# DASHBOARD.net
KiCad netlist of a schematic drawn in EAGLE
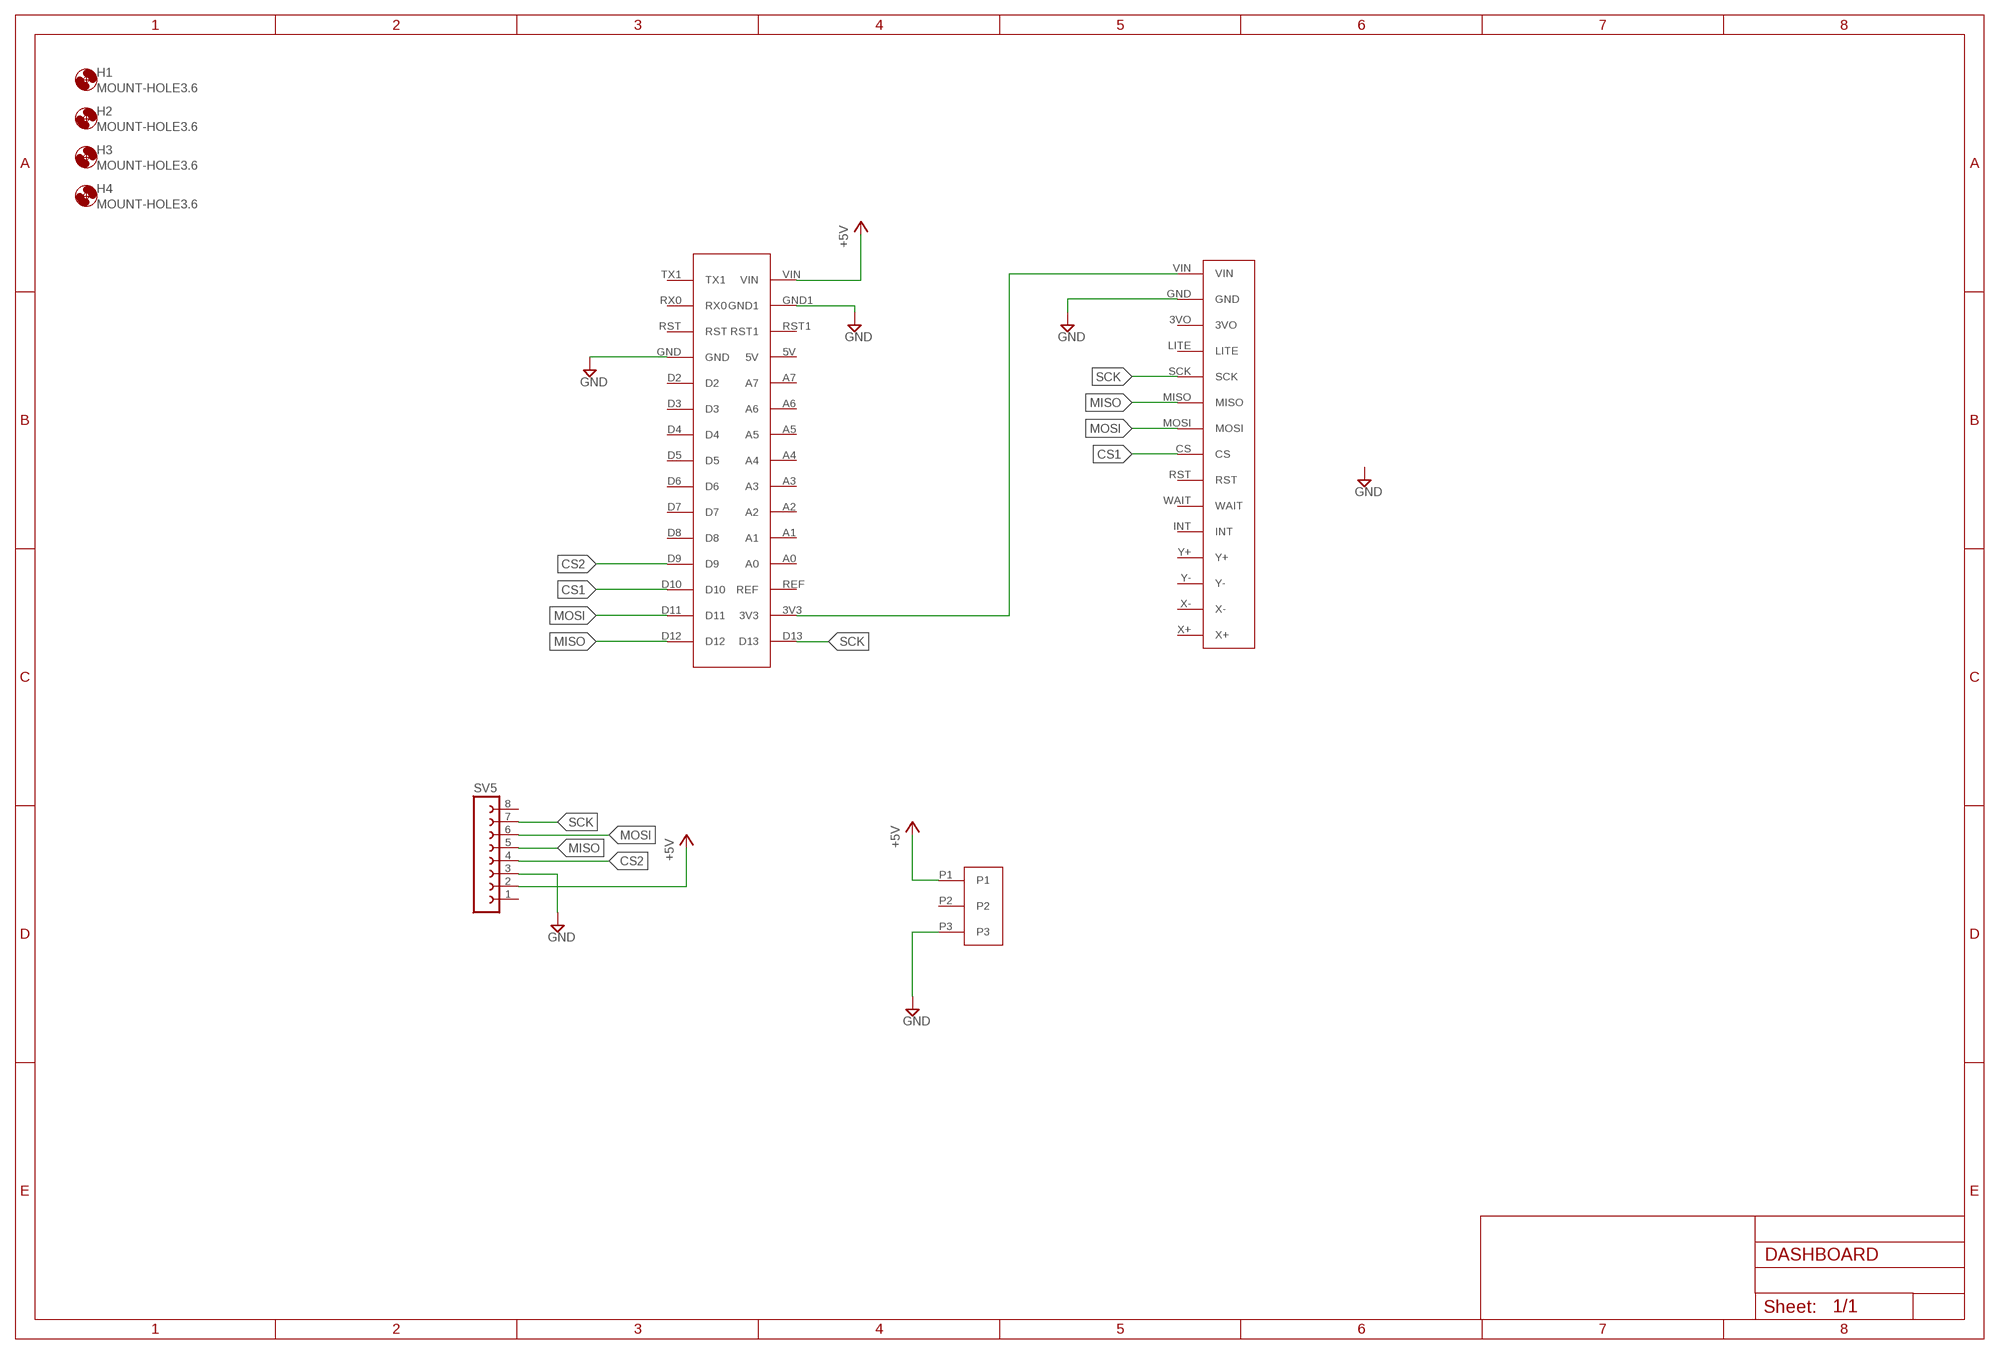
[diagram p0: schematic, sheet 1]

(export (version "E")
  (design (tool "Eeschema 10.0.6"))
  (components
    (comp (ref "H1")
      (value "MOUNT-HOLE3.6")
      (footprint "eagle-import:3,6")
      (libsource (lib "eagle-import") (part "MOUNT-HOLE3.6"))
    )
    (comp (ref "H2")
      (value "MOUNT-HOLE3.6")
      (footprint "eagle-import:3,6")
      (libsource (lib "eagle-import") (part "MOUNT-HOLE3.6"))
    )
    (comp (ref "H3")
      (value "MOUNT-HOLE3.6")
      (footprint "eagle-import:3,6")
      (libsource (lib "eagle-import") (part "MOUNT-HOLE3.6"))
    )
    (comp (ref "H4")
      (value "MOUNT-HOLE3.6")
      (footprint "eagle-import:3,6")
      (libsource (lib "eagle-import") (part "MOUNT-HOLE3.6"))
    )
    (comp (ref "SV5")
      (value "FE08-1")
      (footprint "eagle-import:FE08")
      (libsource (lib "eagle-import") (part "FE08-1"))
    )
    (comp (ref "U$1")
      (value "BREAKOUT")
      (footprint "eagle-import:BREAKOUT")
      (libsource (lib "eagle-import") (part "BREAKOUT"))
    )
    (comp (ref "U$2")
      (value "NANO")
      (footprint "eagle-import:NANO")
      (libsource (lib "eagle-import") (part "NANO"))
    )
    (comp (ref "U$3")
      (value "1935789")
      (footprint "eagle-import:1935789")
      (libsource (lib "eagle-import") (part "1935789"))
    )
  )
  (nets
    (net (code "1") (name "+5V") (class "Default")
      (node (ref "SV5") (pin "2") (pinfunction "2_2") (pintype "passive"))
      (node (ref "U$2") (pin "VIN") (pinfunction "VIN_VIN") (pintype "bidirectional"))
      (node (ref "U$3") (pin "P1") (pinfunction "P1_P1") (pintype "bidirectional"))
    )
    (net (code "2") (name "CS1") (class "Default")
      (node (ref "U$1") (pin "CS") (pinfunction "CS_CS") (pintype "bidirectional"))
      (node (ref "U$2") (pin "D10") (pinfunction "D10_D10") (pintype "bidirectional"))
    )
    (net (code "3") (name "CS2") (class "Default")
      (node (ref "SV5") (pin "4") (pinfunction "4_4") (pintype "passive"))
      (node (ref "U$2") (pin "D9") (pinfunction "D9_D9") (pintype "bidirectional"))
    )
    (net (code "4") (name "GND") (class "Default")
      (node (ref "SV5") (pin "3") (pinfunction "3_3") (pintype "passive"))
      (node (ref "U$1") (pin "GND") (pinfunction "GND_GND") (pintype "bidirectional"))
      (node (ref "U$2") (pin "GND") (pinfunction "GND_GND") (pintype "bidirectional"))
      (node (ref "U$2") (pin "GND1") (pinfunction "GND1_GND1") (pintype "bidirectional"))
      (node (ref "U$3") (pin "P3") (pinfunction "P3_P3") (pintype "bidirectional"))
    )
    (net (code "5") (name "MISO") (class "Default")
      (node (ref "SV5") (pin "5") (pinfunction "5_5") (pintype "passive"))
      (node (ref "U$1") (pin "MISO") (pinfunction "MISO_MISO") (pintype "bidirectional"))
      (node (ref "U$2") (pin "D12") (pinfunction "D12_D12") (pintype "bidirectional"))
    )
    (net (code "6") (name "MOSI") (class "Default")
      (node (ref "SV5") (pin "6") (pinfunction "6_6") (pintype "passive"))
      (node (ref "U$1") (pin "MOSI") (pinfunction "MOSI_MOSI") (pintype "bidirectional"))
      (node (ref "U$2") (pin "D11") (pinfunction "D11_D11") (pintype "bidirectional"))
    )
    (net (code "7") (name "Net-(U$1-PadVIN)") (class "Default")
      (node (ref "U$1") (pin "VIN") (pinfunction "VIN_VIN") (pintype "bidirectional"))
      (node (ref "U$2") (pin "3V3") (pinfunction "3V3_3V3") (pintype "bidirectional"))
    )
    (net (code "8") (name "SCK") (class "Default")
      (node (ref "SV5") (pin "7") (pinfunction "7_7") (pintype "passive"))
      (node (ref "U$1") (pin "SCK") (pinfunction "SCK_SCK") (pintype "bidirectional"))
      (node (ref "U$2") (pin "D13") (pinfunction "D13_D13") (pintype "bidirectional"))
    )
    (net (code "9") (name "unconnected-(SV5-Pad1)") (class "Default")
      (node (ref "SV5") (pin "1") (pinfunction "1_1") (pintype "passive"))
    )
    (net (code "10") (name "unconnected-(SV5-Pad8)") (class "Default")
      (node (ref "SV5") (pin "8") (pinfunction "8_8") (pintype "passive"))
    )
    (net (code "11") (name "unconnected-(U$1-Pad3VO)") (class "Default")
      (node (ref "U$1") (pin "3VO") (pinfunction "3VO_3VO") (pintype "bidirectional"))
    )
    (net (code "12") (name "unconnected-(U$1-PadINT)") (class "Default")
      (node (ref "U$1") (pin "INT") (pinfunction "INT_INT") (pintype "bidirectional"))
    )
    (net (code "13") (name "unconnected-(U$1-PadLITE)") (class "Default")
      (node (ref "U$1") (pin "LITE") (pinfunction "LITE_LITE") (pintype "bidirectional"))
    )
    (net (code "14") (name "unconnected-(U$1-PadRST)") (class "Default")
      (node (ref "U$1") (pin "RST") (pinfunction "RST_RST") (pintype "bidirectional"))
    )
    (net (code "15") (name "unconnected-(U$1-PadWAIT)") (class "Default")
      (node (ref "U$1") (pin "WAIT") (pinfunction "WAIT_WAIT") (pintype "bidirectional"))
    )
    (net (code "16") (name "unconnected-(U$1-PadX+)") (class "Default")
      (node (ref "U$1") (pin "X+") (pinfunction "X+_X+") (pintype "bidirectional"))
    )
    (net (code "17") (name "unconnected-(U$1-PadX-)") (class "Default")
      (node (ref "U$1") (pin "X-") (pinfunction "X-_X-") (pintype "bidirectional"))
    )
    (net (code "18") (name "unconnected-(U$1-PadY+)") (class "Default")
      (node (ref "U$1") (pin "Y+") (pinfunction "Y+_Y+") (pintype "bidirectional"))
    )
    (net (code "19") (name "unconnected-(U$1-PadY-)") (class "Default")
      (node (ref "U$1") (pin "Y-") (pinfunction "Y-_Y-") (pintype "bidirectional"))
    )
    (net (code "20") (name "unconnected-(U$2-Pad5V)") (class "Default")
      (node (ref "U$2") (pin "5V") (pinfunction "5V_5V") (pintype "bidirectional"))
    )
    (net (code "21") (name "unconnected-(U$2-PadA0)") (class "Default")
      (node (ref "U$2") (pin "A0") (pinfunction "A0_A0") (pintype "bidirectional"))
    )
    (net (code "22") (name "unconnected-(U$2-PadA1)") (class "Default")
      (node (ref "U$2") (pin "A1") (pinfunction "A1_A1") (pintype "bidirectional"))
    )
    (net (code "23") (name "unconnected-(U$2-PadA2)") (class "Default")
      (node (ref "U$2") (pin "A2") (pinfunction "A2_A2") (pintype "bidirectional"))
    )
    (net (code "24") (name "unconnected-(U$2-PadA3)") (class "Default")
      (node (ref "U$2") (pin "A3") (pinfunction "A3_A3") (pintype "bidirectional"))
    )
    (net (code "25") (name "unconnected-(U$2-PadA4)") (class "Default")
      (node (ref "U$2") (pin "A4") (pinfunction "A4_A4") (pintype "bidirectional"))
    )
    (net (code "26") (name "unconnected-(U$2-PadA5)") (class "Default")
      (node (ref "U$2") (pin "A5") (pinfunction "A5_A5") (pintype "bidirectional"))
    )
    (net (code "27") (name "unconnected-(U$2-PadA6)") (class "Default")
      (node (ref "U$2") (pin "A6") (pinfunction "A6_A6") (pintype "bidirectional"))
    )
    (net (code "28") (name "unconnected-(U$2-PadA7)") (class "Default")
      (node (ref "U$2") (pin "A7") (pinfunction "A7_A7") (pintype "bidirectional"))
    )
    (net (code "29") (name "unconnected-(U$2-PadD2)") (class "Default")
      (node (ref "U$2") (pin "D2") (pinfunction "D2_D2") (pintype "bidirectional"))
    )
    (net (code "30") (name "unconnected-(U$2-PadD3)") (class "Default")
      (node (ref "U$2") (pin "D3") (pinfunction "D3_D3") (pintype "bidirectional"))
    )
    (net (code "31") (name "unconnected-(U$2-PadD4)") (class "Default")
      (node (ref "U$2") (pin "D4") (pinfunction "D4_D4") (pintype "bidirectional"))
    )
    (net (code "32") (name "unconnected-(U$2-PadD5)") (class "Default")
      (node (ref "U$2") (pin "D5") (pinfunction "D5_D5") (pintype "bidirectional"))
    )
    (net (code "33") (name "unconnected-(U$2-PadD6)") (class "Default")
      (node (ref "U$2") (pin "D6") (pinfunction "D6_D6") (pintype "bidirectional"))
    )
    (net (code "34") (name "unconnected-(U$2-PadD7)") (class "Default")
      (node (ref "U$2") (pin "D7") (pinfunction "D7_D7") (pintype "bidirectional"))
    )
    (net (code "35") (name "unconnected-(U$2-PadD8)") (class "Default")
      (node (ref "U$2") (pin "D8") (pinfunction "D8_D8") (pintype "bidirectional"))
    )
    (net (code "36") (name "unconnected-(U$2-PadREF)") (class "Default")
      (node (ref "U$2") (pin "REF") (pinfunction "REF_REF") (pintype "bidirectional"))
    )
    (net (code "37") (name "unconnected-(U$2-PadRST)") (class "Default")
      (node (ref "U$2") (pin "RST") (pinfunction "RST_RST") (pintype "bidirectional"))
    )
    (net (code "38") (name "unconnected-(U$2-PadRST1)") (class "Default")
      (node (ref "U$2") (pin "RST1") (pinfunction "RST1_RST1") (pintype "bidirectional"))
    )
    (net (code "39") (name "unconnected-(U$2-PadRX0)") (class "Default")
      (node (ref "U$2") (pin "RX0") (pinfunction "RX0_RX0") (pintype "bidirectional"))
    )
    (net (code "40") (name "unconnected-(U$2-PadTX1)") (class "Default")
      (node (ref "U$2") (pin "TX1") (pinfunction "TX1_TX1") (pintype "bidirectional"))
    )
    (net (code "41") (name "unconnected-(U$3-PadP2)") (class "Default")
      (node (ref "U$3") (pin "P2") (pinfunction "P2_P2") (pintype "bidirectional"))
    )
  )
)
